# SubGhz_Module.net
KiCad netlist of a schematic drawn in EasyEDA Pro
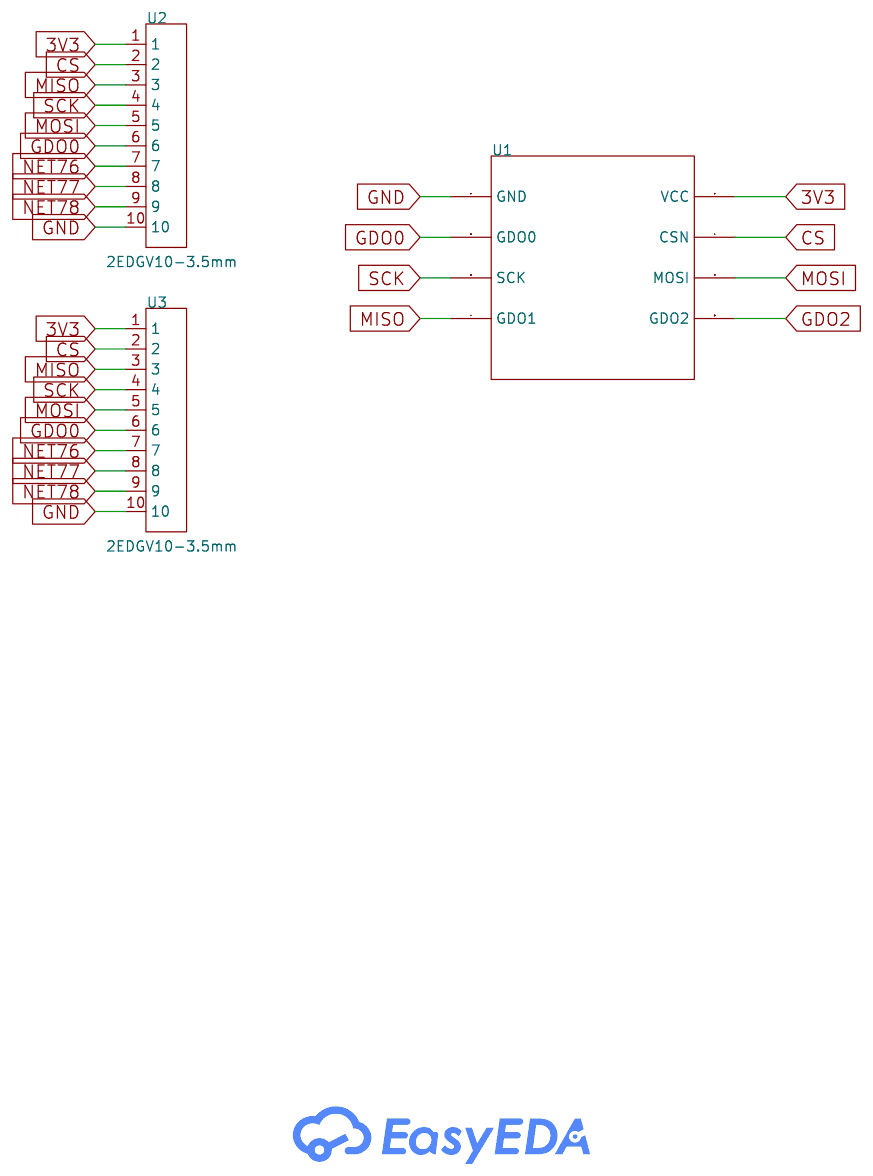
[diagram p0: schematic sheet]

(export (version "E")
  (design (tool "Eeschema 10.0.6"))
  (components
    (comp (ref "U1")
      (value "~")
      (footprint "easyedapro:CC1101-1")
      (libsource (lib "easyedapro") (part "cc1101"))
    )
    (comp (ref "U2")
      (value "2EDGV10-3.5mm")
      (footprint "easyedapro:CONN-TH_10P-P3.50")
      (libsource (lib "easyedapro") (part "CONN-TH_10P-P3.50"))
    )
    (comp (ref "U3")
      (value "2EDGV10-3.5mm")
      (footprint "easyedapro:CONN-TH_10P-P3.50")
      (libsource (lib "easyedapro") (part "CONN-TH_10P-P3.50"))
    )
  )
  (nets
    (net (code "1") (name "3V3") (class "Default")
      (node (ref "U1") (pin "2") (pinfunction "VCC_2") (pintype "input"))
      (node (ref "U2") (pin "1") (pinfunction "1_1") (pintype "unspecified"))
      (node (ref "U3") (pin "1") (pinfunction "1_1") (pintype "unspecified"))
    )
    (net (code "2") (name "CS") (class "Default")
      (node (ref "U1") (pin "4") (pinfunction "CSN_4") (pintype "input"))
      (node (ref "U2") (pin "2") (pinfunction "2_2") (pintype "unspecified"))
      (node (ref "U3") (pin "2") (pinfunction "2_2") (pintype "unspecified"))
    )
    (net (code "3") (name "GDO0") (class "Default")
      (node (ref "U1") (pin "3") (pinfunction "GDO0_3") (pintype "input"))
      (node (ref "U2") (pin "6") (pinfunction "6_6") (pintype "unspecified"))
      (node (ref "U3") (pin "6") (pinfunction "6_6") (pintype "unspecified"))
    )
    (net (code "4") (name "GDO2") (class "Default")
      (node (ref "U1") (pin "8") (pinfunction "GDO2_8") (pintype "input"))
    )
    (net (code "5") (name "GND") (class "Default")
      (node (ref "U1") (pin "1") (pinfunction "GND_1") (pintype "input"))
      (node (ref "U2") (pin "10") (pinfunction "10_10") (pintype "unspecified"))
      (node (ref "U3") (pin "10") (pinfunction "10_10") (pintype "unspecified"))
    )
    (net (code "6") (name "MISO") (class "Default")
      (node (ref "U1") (pin "7") (pinfunction "GDO1_7") (pintype "input"))
      (node (ref "U2") (pin "3") (pinfunction "3_3") (pintype "unspecified"))
      (node (ref "U3") (pin "3") (pinfunction "3_3") (pintype "unspecified"))
    )
    (net (code "7") (name "MOSI") (class "Default")
      (node (ref "U1") (pin "6") (pinfunction "MOSI_6") (pintype "input"))
      (node (ref "U2") (pin "5") (pinfunction "5_5") (pintype "unspecified"))
      (node (ref "U3") (pin "5") (pinfunction "5_5") (pintype "unspecified"))
    )
    (net (code "8") (name "NET76") (class "Default")
      (node (ref "U2") (pin "7") (pinfunction "7_7") (pintype "unspecified"))
      (node (ref "U3") (pin "7") (pinfunction "7_7") (pintype "unspecified"))
    )
    (net (code "9") (name "NET77") (class "Default")
      (node (ref "U2") (pin "8") (pinfunction "8_8") (pintype "unspecified"))
      (node (ref "U3") (pin "8") (pinfunction "8_8") (pintype "unspecified"))
    )
    (net (code "10") (name "NET78") (class "Default")
      (node (ref "U2") (pin "9") (pinfunction "9_9") (pintype "unspecified"))
      (node (ref "U3") (pin "9") (pinfunction "9_9") (pintype "unspecified"))
    )
    (net (code "11") (name "SCK") (class "Default")
      (node (ref "U1") (pin "5") (pinfunction "SCK_5") (pintype "input"))
      (node (ref "U2") (pin "4") (pinfunction "4_4") (pintype "unspecified"))
      (node (ref "U3") (pin "4") (pinfunction "4_4") (pintype "unspecified"))
    )
  )
)
